# 03_POWER1.net
KiCad netlist of a schematic drawn in Altium Designer
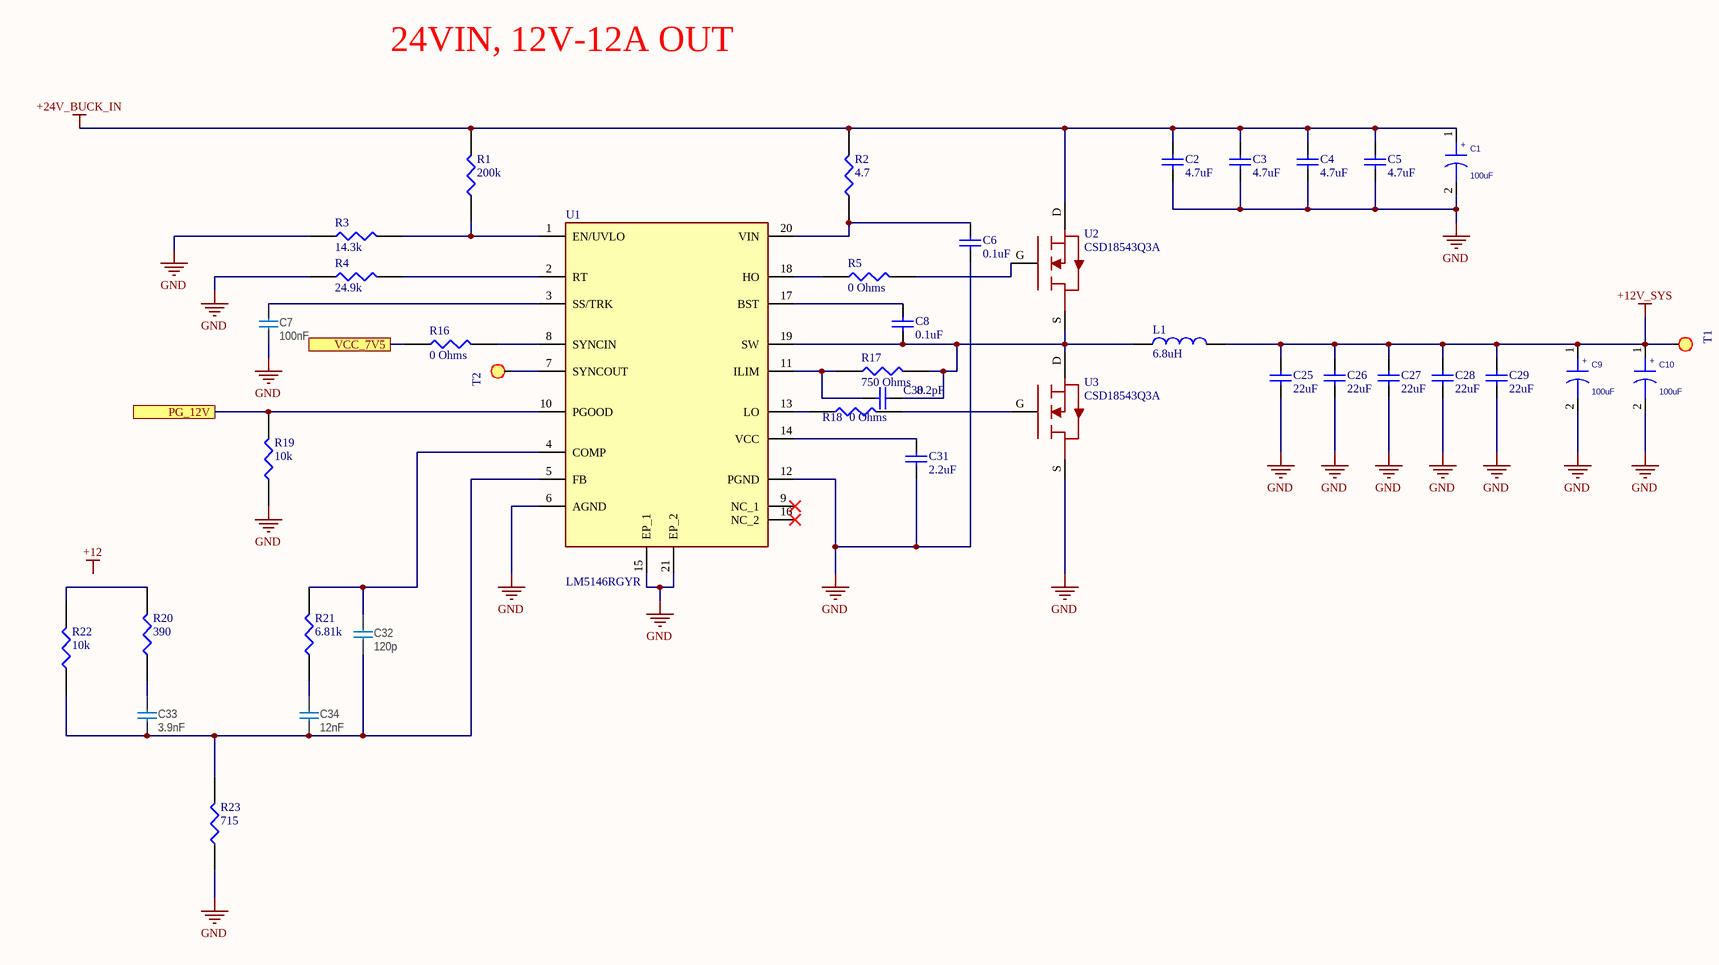
[diagram p0: 03_POWER1.SchDoc]

(export (version "E")
  (design (tool "Eeschema 10.0.6"))
  (components
    (comp (ref "C1")
      (value "100uF")
      (footprint "SMD 10.3x10.3x10.0mm")
      (description "CAP ALUM POLY 100UF 20% 50V SMD")
      (fields
        (field (name "MANUFACTURER") "Nichicon")
        (field (name "MANUFACTURER PART NUMBER") "PCV1H101MCL2GS")
      )
      (libsource (lib "HW_ADHERENT_SYSCTRL_R1_L2") (part "150uF-6.3V-20%-AL-LOESR-SMD_5x6_5"))
    )
    (comp (ref "C2")
      (value "4.7uF")
      (footprint "CAP1206")
      (description "4.7 µF ±10% 100V Ceramic Capacitor X7S 1206 (3216 Metric)")
      (fields (field (name "MANUFACTURER PART NUMBER") "12061Z475KAT2A"))
      (libsource (lib "HW_ADHERENT_SYSCTRL_R1_L2") (part "CAP1206_4.7uF_100V"))
    )
    (comp (ref "C3")
      (value "4.7uF")
      (footprint "CAP1206")
      (description "4.7 µF ±10% 100V Ceramic Capacitor X7S 1206 (3216 Metric)")
      (fields (field (name "MANUFACTURER PART NUMBER") "12061Z475KAT2A"))
      (libsource (lib "HW_ADHERENT_SYSCTRL_R1_L2") (part "CAP1206_4.7uF_100V"))
    )
    (comp (ref "C4")
      (value "4.7uF")
      (footprint "CAP1206")
      (description "4.7 µF ±10% 100V Ceramic Capacitor X7S 1206 (3216 Metric)")
      (fields (field (name "MANUFACTURER PART NUMBER") "12061Z475KAT2A"))
      (libsource (lib "HW_ADHERENT_SYSCTRL_R1_L2") (part "CAP1206_4.7uF_100V"))
    )
    (comp (ref "C5")
      (value "4.7uF")
      (footprint "CAP1206")
      (description "4.7 µF ±10% 100V Ceramic Capacitor X7S 1206 (3216 Metric)")
      (fields (field (name "MANUFACTURER PART NUMBER") "12061Z475KAT2A"))
      (libsource (lib "HW_ADHERENT_SYSCTRL_R1_L2") (part "CAP1206_4.7uF_100V"))
    )
    (comp (ref "C6")
      (value "0.1uF")
      (footprint "0402_C")
      (description "CAP CER 0.1UF 50V X7R 0402")
      (fields
        (field (name "MANUFACTURER") "TDK Corporation")
        (field (name "MANUFACTURER PART NUMBER") "C1005X7R1H104K050BB")
      )
      (libsource (lib "HW_ADHERENT_SYSCTRL_R1_L3") (part "Cap"))
    )
    (comp (ref "C7")
      (value "100nF")
      (footprint "CAPC0603X03L_C")
      (description "Capacitor, X5R, ±10%")
      (fields
        (field (name "PART NUMBER") "C0201-100n")
        (field (name "MANUFACTURER") "N.A.")
        (field (name "AUTHOR") "rsk")
      )
      (libsource (lib "HW_ADHERENT_SYSCTRL_R1_L1") (part "C0201-100n"))
    )
    (comp (ref "C8")
      (value "0.1uF")
      (footprint "0402_C")
      (description "CAP CER 0.1UF 50V X7R 0402")
      (fields
        (field (name "MANUFACTURER") "TDK Corporation")
        (field (name "MANUFACTURER PART NUMBER") "C1005X7R1H104K050BB")
      )
      (libsource (lib "HW_ADHERENT_SYSCTRL_R1_L3") (part "Cap"))
    )
    (comp (ref "C9")
      (value "100uF")
      (footprint "SMD 10.3x10.3x10.0mm")
      (description "CAP ALUM POLY 100UF 20% 50V SMD")
      (fields
        (field (name "MANUFACTURER") "Nichicon")
        (field (name "MANUFACTURER PART NUMBER") "PCV1H101MCL2GS")
      )
      (libsource (lib "HW_ADHERENT_SYSCTRL_R1_L2") (part "150uF-6.3V-20%-AL-LOESR-SMD_5x6_5"))
    )
    (comp (ref "C10")
      (value "100uF")
      (footprint "SMD 10.3x10.3x10.0mm")
      (description "CAP ALUM POLY 100UF 20% 50V SMD")
      (fields
        (field (name "MANUFACTURER") "Nichicon")
        (field (name "MANUFACTURER PART NUMBER") "PCV1H101MCL2GS")
      )
      (libsource (lib "HW_ADHERENT_SYSCTRL_R1_L2") (part "150uF-6.3V-20%-AL-LOESR-SMD_5x6_5"))
    )
    (comp (ref "C25")
      (value "22uF")
      (footprint "CAP1206")
      (description "22 µF ±20% 35V Ceramic Capacitor X5R 1206 (3216 Metric)")
      (fields (field (name "MANUFACTURER PART NUMBER") "C3216X5R1V226M160AC"))
      (libsource (lib "HW_ADHERENT_SYSCTRL_R1_L2") (part "CAP1206_22uF_35V"))
    )
    (comp (ref "C26")
      (value "22uF")
      (footprint "CAP1206")
      (description "22 µF ±20% 35V Ceramic Capacitor X5R 1206 (3216 Metric)")
      (fields (field (name "MANUFACTURER PART NUMBER") "C3216X5R1V226M160AC"))
      (libsource (lib "HW_ADHERENT_SYSCTRL_R1_L2") (part "CAP1206_22uF_35V"))
    )
    (comp (ref "C27")
      (value "22uF")
      (footprint "CAP1206")
      (description "22 µF ±20% 35V Ceramic Capacitor X5R 1206 (3216 Metric)")
      (fields (field (name "MANUFACTURER PART NUMBER") "C3216X5R1V226M160AC"))
      (libsource (lib "HW_ADHERENT_SYSCTRL_R1_L2") (part "CAP1206_22uF_35V"))
    )
    (comp (ref "C28")
      (value "22uF")
      (footprint "CAP1206")
      (description "22 µF ±20% 35V Ceramic Capacitor X5R 1206 (3216 Metric)")
      (fields (field (name "MANUFACTURER PART NUMBER") "C3216X5R1V226M160AC"))
      (libsource (lib "HW_ADHERENT_SYSCTRL_R1_L2") (part "CAP1206_22uF_35V"))
    )
    (comp (ref "C29")
      (value "22uF")
      (footprint "CAP1206")
      (description "22 µF ±20% 35V Ceramic Capacitor X5R 1206 (3216 Metric)")
      (fields (field (name "MANUFACTURER PART NUMBER") "C3216X5R1V226M160AC"))
      (libsource (lib "HW_ADHERENT_SYSCTRL_R1_L2") (part "CAP1206_22uF_35V"))
    )
    (comp (ref "C30")
      (value "8.2pF")
      (footprint "SMC0603")
      (description "8.2 pF ±0.25pF 50V Ceramic Capacitor C0G, NP0 0603 (1608 Metric)")
      (fields
        (field (name "MANUFACTURER PART NUMBER") "CC0603CRNPO9BN8R2")
        (field (name "LCSC PART NUMBER") "C277519")
      )
      (libsource (lib "HW_ADHERENT_SYSCTRL_R1_L2") (part "CAP0603_8.2PF_50V"))
    )
    (comp (ref "C31")
      (value "2.2uF")
      (footprint "SMC0603")
      (description "2.2 µF ±10% 16V Ceramic Capacitor X7S 0603 (1608 Metric)")
      (fields
        (field (name "MANUFACTURER PART NUMBER") "GRT188C71C225KE13D")
        (field (name "Comment") "CAP CER 4.7UF 25V X5R 0603")
      )
      (libsource (lib "HW_ADHERENT_SYSCTRL_R1_L2") (part "CAP0603_2.2UF_16V"))
    )
    (comp (ref "C32")
      (value "120p")
      (footprint "CAPC0603X03L_C")
      (description "Capacitor, X5R, ±10%")
      (fields
        (field (name "PART NUMBER") "C0201-100n")
        (field (name "MANUFACTURER") "N.A.")
        (field (name "AUTHOR") "rsk")
      )
      (libsource (lib "HW_ADHERENT_SYSCTRL_R1_L1") (part "C0201-100n"))
    )
    (comp (ref "C33")
      (value "3.9nF")
      (footprint "CAPC0603X03L_C")
      (description "Capacitor, X5R, ±10%")
      (fields
        (field (name "PART NUMBER") "C0201-100n")
        (field (name "MANUFACTURER") "N.A.")
        (field (name "AUTHOR") "rsk")
      )
      (libsource (lib "HW_ADHERENT_SYSCTRL_R1_L1") (part "C0201-100n"))
    )
    (comp (ref "C34")
      (value "12nF")
      (footprint "CAPC0603X03L_C")
      (description "Capacitor, X5R, ±10%")
      (fields
        (field (name "PART NUMBER") "C0201-100n")
        (field (name "MANUFACTURER") "N.A.")
        (field (name "AUTHOR") "rsk")
      )
      (libsource (lib "HW_ADHERENT_SYSCTRL_R1_L1") (part "C0201-100n"))
    )
    (comp (ref "L1")
      (value "6.8uH")
      (footprint "SRU10386R2Y")
      (description "6.2 µH Shielded Drum Core, Wirewound Inductor 4 A 16.5mOhm Nonstandard")
      (fields
        (field (name "MANUFACTURER PART NUMBER") "SRU1038-6R2Y")
        (field (name "MOUSER PART NUMBER") "652-SRU1038-6R2Y")
      )
      (libsource (lib "HW_ADHERENT_SYSCTRL_R1_L2") (part "IND_6.2uH_4A"))
    )
    (comp (ref "R1")
      (value "200k")
      (footprint "0805")
      (libsource (lib "HW_ADHERENT_SYSCTRL_R1_L1") (part "0805W8F2003T5E"))
    )
    (comp (ref "R2")
      (value "4.7")
      (footprint "0805")
      (libsource (lib "HW_ADHERENT_SYSCTRL_R1_L1") (part "0805W8F2003T5E"))
    )
    (comp (ref "R3")
      (value "14.3k")
      (footprint "0805")
      (libsource (lib "HW_ADHERENT_SYSCTRL_R1_L1") (part "0805W8F2003T5E"))
    )
    (comp (ref "R4")
      (value "24.9k")
      (footprint "0805")
      (libsource (lib "HW_ADHERENT_SYSCTRL_R1_L1") (part "0805W8F2003T5E"))
    )
    (comp (ref "R5")
      (value "0 Ohms")
      (footprint "0805")
      (libsource (lib "HW_ADHERENT_SYSCTRL_R1_L1") (part "0805W8F2003T5E"))
    )
    (comp (ref "R16")
      (value "0 Ohms")
      (footprint "0805")
      (libsource (lib "HW_ADHERENT_SYSCTRL_R1_L1") (part "0805W8F2003T5E"))
    )
    (comp (ref "R17")
      (value "750 Ohms")
      (footprint "0805")
      (libsource (lib "HW_ADHERENT_SYSCTRL_R1_L1") (part "0805W8F2003T5E"))
    )
    (comp (ref "R18")
      (value "0 Ohms")
      (footprint "0805")
      (libsource (lib "HW_ADHERENT_SYSCTRL_R1_L1") (part "0805W8F2003T5E"))
    )
    (comp (ref "R19")
      (value "10k")
      (footprint "0805")
      (libsource (lib "HW_ADHERENT_SYSCTRL_R1_L1") (part "0805W8F2003T5E"))
    )
    (comp (ref "R20")
      (value "390")
      (footprint "0805")
      (libsource (lib "HW_ADHERENT_SYSCTRL_R1_L1") (part "0805W8F2003T5E"))
    )
    (comp (ref "R21")
      (value "6.81k")
      (footprint "0805")
      (libsource (lib "HW_ADHERENT_SYSCTRL_R1_L1") (part "0805W8F2003T5E"))
    )
    (comp (ref "R22")
      (value "10k")
      (footprint "0805")
      (libsource (lib "HW_ADHERENT_SYSCTRL_R1_L1") (part "0805W8F2003T5E"))
    )
    (comp (ref "R23")
      (value "715")
      (footprint "0805")
      (libsource (lib "HW_ADHERENT_SYSCTRL_R1_L1") (part "0805W8F2003T5E"))
    )
    (comp (ref "T1")
      (value "SMD")
      (footprint "TEST_POINT")
      (libsource (lib "HW_ADHERENT_SYSCTRL_R1_L2") (part "TP_15"))
    )
    (comp (ref "T2")
      (value "SMD")
      (footprint "TEST_POINT")
      (libsource (lib "HW_ADHERENT_SYSCTRL_R1_L2") (part "TP_15"))
    )
    (comp (ref "U1")
      (value "LM5146RGYR")
      (footprint "LM5146RGYR")
      (description "Buck Regulator Positive Output Step-Down DC-DC Controller IC 20-VQFN (3.5x4.5)")
      (fields (field (name "MANUFACTURER") "Texas Instruments"))
      (libsource (lib "HW_ADHERENT_SYSCTRL_R1_L1") (part "LM5146RGYR"))
    )
    (comp (ref "U2")
      (value "CSD18543Q3A")
      (footprint "CSD18543Q3A")
      (description "N-Channel 60 V 60A (Tc) 66W (Tc) Surface Mount 8-VSONP (3x3.3)")
      (libsource (lib "HW_ADHERENT_SYSCTRL_R1_L1") (part "CSD18543Q3A"))
    )
    (comp (ref "U3")
      (value "CSD18543Q3A")
      (footprint "CSD18543Q3A")
      (description "N-Channel 60 V 60A (Tc) 66W (Tc) Surface Mount 8-VSONP (3x3.3)")
      (libsource (lib "HW_ADHERENT_SYSCTRL_R1_L1") (part "CSD18543Q3A"))
    )
  )
  (nets
    (net (code "2") (name "+12V_SYS") (class "Default")
      (node (ref "C10") (pin "1") (pinfunction "1_1") (pintype "passive"))
      (node (ref "C25") (pin "2") (pinfunction "2_2") (pintype "passive"))
      (node (ref "C26") (pin "2") (pinfunction "2_2") (pintype "passive"))
      (node (ref "C27") (pin "2") (pinfunction "2_2") (pintype "passive"))
      (node (ref "C28") (pin "2") (pinfunction "2_2") (pintype "passive"))
      (node (ref "C29") (pin "2") (pinfunction "2_2") (pintype "passive"))
      (node (ref "C9") (pin "1") (pinfunction "1_1") (pintype "passive"))
      (node (ref "L1") (pin "2") (pinfunction "2_2") (pintype "passive"))
      (node (ref "T1") (pin "1") (pinfunction "TP_1") (pintype "passive"))
    )
    (net (code "3") (name "+24V_BUCK_IN") (class "Default")
      (node (ref "C1") (pin "1") (pinfunction "1_1") (pintype "passive"))
      (node (ref "C2") (pin "2") (pinfunction "2_2") (pintype "passive"))
      (node (ref "C3") (pin "2") (pinfunction "2_2") (pintype "passive"))
      (node (ref "C4") (pin "2") (pinfunction "2_2") (pintype "passive"))
      (node (ref "C5") (pin "2") (pinfunction "2_2") (pintype "passive"))
      (node (ref "R1") (pin "2") (pinfunction "2_2") (pintype "passive"))
      (node (ref "R2") (pin "2") (pinfunction "2_2") (pintype "passive"))
      (node (ref "U2") (pin "D") (pinfunction "D_D") (pintype "passive"))
    )
    (net (code "4") (name "/PG_12V") (class "Default")
      (node (ref "R19") (pin "2") (pinfunction "2_2") (pintype "passive"))
      (node (ref "U1") (pin "10") (pinfunction "PGOOD_10") (pintype "passive"))
    )
    (net (code "5") (name "/VCC_7V5") (class "Default")
      (node (ref "R16") (pin "1") (pinfunction "1_1") (pintype "passive"))
    )
    (net (code "6") (name "GND") (class "Default")
      (node (ref "C1") (pin "2") (pinfunction "2_2") (pintype "passive"))
      (node (ref "C10") (pin "2") (pinfunction "2_2") (pintype "passive"))
      (node (ref "C2") (pin "1") (pinfunction "1_1") (pintype "passive"))
      (node (ref "C25") (pin "1") (pinfunction "1_1") (pintype "passive"))
      (node (ref "C26") (pin "1") (pinfunction "1_1") (pintype "passive"))
      (node (ref "C27") (pin "1") (pinfunction "1_1") (pintype "passive"))
      (node (ref "C28") (pin "1") (pinfunction "1_1") (pintype "passive"))
      (node (ref "C29") (pin "1") (pinfunction "1_1") (pintype "passive"))
      (node (ref "C3") (pin "1") (pinfunction "1_1") (pintype "passive"))
      (node (ref "C31") (pin "1") (pinfunction "1_1") (pintype "passive"))
      (node (ref "C4") (pin "1") (pinfunction "1_1") (pintype "passive"))
      (node (ref "C5") (pin "1") (pinfunction "1_1") (pintype "passive"))
      (node (ref "C6") (pin "1") (pinfunction "1_1") (pintype "passive"))
      (node (ref "C7") (pin "1") (pinfunction "1_1") (pintype "passive"))
      (node (ref "C9") (pin "2") (pinfunction "2_2") (pintype "passive"))
      (node (ref "R19") (pin "1") (pinfunction "1_1") (pintype "passive"))
      (node (ref "R23") (pin "1") (pinfunction "1_1") (pintype "passive"))
      (node (ref "R3") (pin "1") (pinfunction "1_1") (pintype "passive"))
      (node (ref "R4") (pin "1") (pinfunction "1_1") (pintype "passive"))
      (node (ref "U1") (pin "12") (pinfunction "PGND_12") (pintype "passive"))
      (node (ref "U1") (pin "15") (pinfunction "EP_1_15") (pintype "passive"))
      (node (ref "U1") (pin "21") (pinfunction "EP_2_21") (pintype "passive"))
      (node (ref "U1") (pin "6") (pinfunction "AGND_6") (pintype "passive"))
      (node (ref "U3") (pin "S") (pinfunction "S_S") (pintype "passive"))
    )
    (net (code "7") (name "Net-(C33-Pad2)") (class "Default")
      (node (ref "C33") (pin "2") (pinfunction "2_2") (pintype "passive"))
      (node (ref "R20") (pin "1") (pinfunction "1_1") (pintype "passive"))
    )
    (net (code "8") (name "Net-(C34-Pad2)") (class "Default")
      (node (ref "C34") (pin "2") (pinfunction "2_2") (pintype "passive"))
      (node (ref "R21") (pin "1") (pinfunction "1_1") (pintype "passive"))
    )
    (net (code "9") (name "Net-(R5-Pad2)") (class "Default")
      (node (ref "R5") (pin "2") (pinfunction "2_2") (pintype "passive"))
      (node (ref "U2") (pin "G") (pinfunction "G_G") (pintype "passive"))
    )
    (net (code "10") (name "Net-(R18-Pad2)") (class "Default")
      (node (ref "R18") (pin "2") (pinfunction "2_2") (pintype "passive"))
      (node (ref "U3") (pin "G") (pinfunction "G_G") (pintype "passive"))
    )
    (net (code "11") (name "Net-(R20-Pad2)") (class "Default")
      (node (ref "R20") (pin "2") (pinfunction "2_2") (pintype "passive"))
      (node (ref "R22") (pin "2") (pinfunction "2_2") (pintype "passive"))
    )
    (net (code "12") (name "Net-(T2-TP)") (class "Default")
      (node (ref "T2") (pin "1") (pinfunction "TP_1") (pintype "passive"))
      (node (ref "U1") (pin "7") (pinfunction "SYNCOUT_7") (pintype "passive"))
    )
    (net (code "13") (name "Net-(U1-BST)") (class "Default")
      (node (ref "C8") (pin "2") (pinfunction "2_2") (pintype "passive"))
      (node (ref "U1") (pin "17") (pinfunction "BST_17") (pintype "passive"))
    )
    (net (code "14") (name "Net-(U1-COMP)") (class "Default")
      (node (ref "C32") (pin "2") (pinfunction "2_2") (pintype "passive"))
      (node (ref "R21") (pin "2") (pinfunction "2_2") (pintype "passive"))
      (node (ref "U1") (pin "4") (pinfunction "COMP_4") (pintype "passive"))
    )
    (net (code "15") (name "Net-(U1-EN{slash}UVLO)") (class "Default")
      (node (ref "R1") (pin "1") (pinfunction "1_1") (pintype "passive"))
      (node (ref "R3") (pin "2") (pinfunction "2_2") (pintype "passive"))
      (node (ref "U1") (pin "1") (pinfunction "EN/UVLO_1") (pintype "passive"))
    )
    (net (code "16") (name "Net-(U1-FB)") (class "Default")
      (node (ref "C32") (pin "1") (pinfunction "1_1") (pintype "passive"))
      (node (ref "C33") (pin "1") (pinfunction "1_1") (pintype "passive"))
      (node (ref "C34") (pin "1") (pinfunction "1_1") (pintype "passive"))
      (node (ref "R22") (pin "1") (pinfunction "1_1") (pintype "passive"))
      (node (ref "R23") (pin "2") (pinfunction "2_2") (pintype "passive"))
      (node (ref "U1") (pin "5") (pinfunction "FB_5") (pintype "passive"))
    )
    (net (code "17") (name "Net-(U1-HO)") (class "Default")
      (node (ref "R5") (pin "1") (pinfunction "1_1") (pintype "passive"))
      (node (ref "U1") (pin "18") (pinfunction "HO_18") (pintype "passive"))
    )
    (net (code "18") (name "Net-(U1-ILIM)") (class "Default")
      (node (ref "C30") (pin "1") (pinfunction "1_1") (pintype "passive"))
      (node (ref "R17") (pin "1") (pinfunction "1_1") (pintype "passive"))
      (node (ref "U1") (pin "11") (pinfunction "ILIM_11") (pintype "passive"))
    )
    (net (code "19") (name "Net-(U1-LO)") (class "Default")
      (node (ref "R18") (pin "1") (pinfunction "1_1") (pintype "passive"))
      (node (ref "U1") (pin "13") (pinfunction "LO_13") (pintype "passive"))
    )
    (net (code "20") (name "Net-(U1-RT)") (class "Default")
      (node (ref "R4") (pin "2") (pinfunction "2_2") (pintype "passive"))
      (node (ref "U1") (pin "2") (pinfunction "RT_2") (pintype "passive"))
    )
    (net (code "21") (name "Net-(U1-SS{slash}TRK)") (class "Default")
      (node (ref "C7") (pin "2") (pinfunction "2_2") (pintype "passive"))
      (node (ref "U1") (pin "3") (pinfunction "SS/TRK_3") (pintype "passive"))
    )
    (net (code "22") (name "Net-(U1-SW)") (class "Default")
      (node (ref "C30") (pin "2") (pinfunction "2_2") (pintype "passive"))
      (node (ref "C8") (pin "1") (pinfunction "1_1") (pintype "passive"))
      (node (ref "L1") (pin "1") (pinfunction "1_1") (pintype "passive"))
      (node (ref "R17") (pin "2") (pinfunction "2_2") (pintype "passive"))
      (node (ref "U1") (pin "19") (pinfunction "SW_19") (pintype "passive"))
      (node (ref "U2") (pin "S") (pinfunction "S_S") (pintype "passive"))
      (node (ref "U3") (pin "D") (pinfunction "D_D") (pintype "passive"))
    )
    (net (code "23") (name "Net-(U1-SYNCIN)") (class "Default")
      (node (ref "R16") (pin "2") (pinfunction "2_2") (pintype "passive"))
      (node (ref "U1") (pin "8") (pinfunction "SYNCIN_8") (pintype "passive"))
    )
    (net (code "24") (name "Net-(U1-VCC)") (class "Default")
      (node (ref "C31") (pin "2") (pinfunction "2_2") (pintype "passive"))
      (node (ref "U1") (pin "14") (pinfunction "VCC_14") (pintype "passive"))
    )
    (net (code "25") (name "Net-(U1-VIN)") (class "Default")
      (node (ref "C6") (pin "2") (pinfunction "2_2") (pintype "passive"))
      (node (ref "R2") (pin "1") (pinfunction "1_1") (pintype "passive"))
      (node (ref "U1") (pin "20") (pinfunction "VIN_20") (pintype "passive"))
    )
    (net (code "26") (name "unconnected-(U1-NC_1-Pad9)") (class "Default")
      (node (ref "U1") (pin "9") (pinfunction "NC_1_9") (pintype "passive+no_connect"))
    )
    (net (code "27") (name "unconnected-(U1-NC_2-Pad16)") (class "Default")
      (node (ref "U1") (pin "16") (pinfunction "NC_2_16") (pintype "passive+no_connect"))
    )
  )
)
